# VOLTAGE_PEAK_V2.net
KiCad netlist of a schematic drawn in Altium Designer
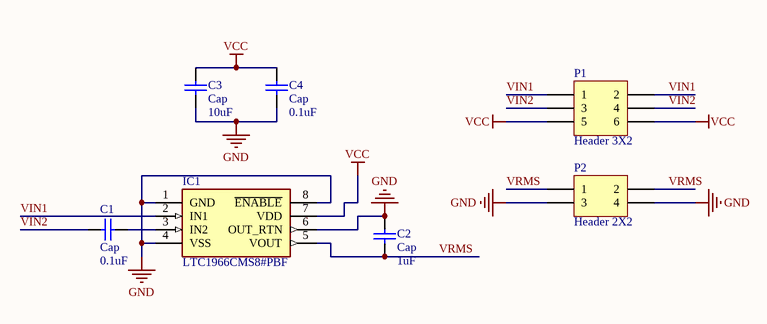
[diagram p0: VOLTAGE_PEAK_V2.SchDoc]

(export (version "E")
  (design (tool "Eeschema 10.0.6"))
  (components
    (comp (ref "C1")
      (value "Cap")
      (footprint "1608[0603]")
      (description "Capacitor")
      (fields (field (name "ALTIUM_VALUE") "0.1uF") (field (name "PUBLISHER") "Altium Limited"))
      (libsource (lib "Miscellaneous Devices") (part "Cap"))
    )
    (comp (ref "C2")
      (value "Cap")
      (footprint "1608[0603]")
      (description "Capacitor")
      (fields (field (name "ALTIUM_VALUE") "1uF") (field (name "PUBLISHER") "Altium Limited"))
      (libsource (lib "Miscellaneous Devices") (part "Cap"))
    )
    (comp (ref "C3")
      (value "Cap")
      (footprint "1608[0603]")
      (description "Capacitor")
      (fields (field (name "ALTIUM_VALUE") "10uF") (field (name "PUBLISHER") "Altium Limited"))
      (libsource (lib "Miscellaneous Devices") (part "Cap"))
    )
    (comp (ref "C4")
      (value "Cap")
      (footprint "1608[0603]")
      (description "Capacitor")
      (fields (field (name "ALTIUM_VALUE") "0.1uF") (field (name "PUBLISHER") "Altium Limited"))
      (libsource (lib "Miscellaneous Devices") (part "Cap"))
    )
    (comp (ref "IC1")
      (value "LTC1966CMS8#PBF")
      (footprint "SamacSys:SOP65P490X110-8N")
      (description "Integrated Circuit")
      (fields (field (name "RS PART NUMBER") "7619266P"))
      (libsource (lib "*") (part "LTC1966CMS8#PBF"))
    )
    (comp (ref "P1")
      (value "Header 3X2")
      (footprint "HDR2X3")
      (description "Header, 3-Pin, Dual row")
      (fields (field (name "PUBLISHER") "Altium Limited"))
      (libsource (lib "Miscellaneous Connectors") (part "Header 3X2"))
    )
    (comp (ref "P2")
      (value "Header 2X2")
      (footprint "HDR2X2")
      (description "Header, 2-Pin, Dual row")
      (fields (field (name "PUBLISHER") "Altium Limited"))
      (libsource (lib "Miscellaneous Connectors") (part "Header 2X2"))
    )
  )
  (nets
    (net (code "1") (name "/VIN1") (class "Default")
      (node (ref "IC1") (pin "2") (pinfunction "IN1_2") (pintype "input"))
      (node (ref "P1") (pin "1") (pinfunction "1_1") (pintype "passive"))
      (node (ref "P1") (pin "2") (pinfunction "2_2") (pintype "passive"))
    )
    (net (code "2") (name "/VIN2") (class "Default")
      (node (ref "C1") (pin "1") (pinfunction "1_1") (pintype "passive"))
      (node (ref "P1") (pin "3") (pinfunction "3_3") (pintype "passive"))
      (node (ref "P1") (pin "4") (pinfunction "4_4") (pintype "passive"))
    )
    (net (code "3") (name "/VRMS") (class "Default")
      (node (ref "C2") (pin "1") (pinfunction "1_1") (pintype "passive"))
      (node (ref "IC1") (pin "5") (pinfunction "VOUT_5") (pintype "output"))
      (node (ref "P2") (pin "1") (pinfunction "1_1") (pintype "passive"))
      (node (ref "P2") (pin "2") (pinfunction "2_2") (pintype "passive"))
    )
    (net (code "4") (name "GND") (class "Default")
      (node (ref "C2") (pin "2") (pinfunction "2_2") (pintype "passive"))
      (node (ref "C3") (pin "1") (pinfunction "1_1") (pintype "passive"))
      (node (ref "C4") (pin "1") (pinfunction "1_1") (pintype "passive"))
      (node (ref "IC1") (pin "1") (pinfunction "GND_1") (pintype "power_in"))
      (node (ref "IC1") (pin "4") (pinfunction "VSS_4") (pintype "power_in"))
      (node (ref "IC1") (pin "6") (pinfunction "OUT_RTN_6") (pintype "output"))
      (node (ref "IC1") (pin "8") (pinfunction "~{ENABLE}_8") (pintype "passive"))
      (node (ref "P2") (pin "3") (pinfunction "3_3") (pintype "passive"))
      (node (ref "P2") (pin "4") (pinfunction "4_4") (pintype "passive"))
    )
    (net (code "5") (name "Net-(IC1-IN2)") (class "Default")
      (node (ref "C1") (pin "2") (pinfunction "2_2") (pintype "passive"))
      (node (ref "IC1") (pin "3") (pinfunction "IN2_3") (pintype "input"))
    )
    (net (code "6") (name "VCC") (class "Default")
      (node (ref "C3") (pin "2") (pinfunction "2_2") (pintype "passive"))
      (node (ref "C4") (pin "2") (pinfunction "2_2") (pintype "passive"))
      (node (ref "IC1") (pin "7") (pinfunction "VDD_7") (pintype "power_in"))
      (node (ref "P1") (pin "5") (pinfunction "5_5") (pintype "passive"))
      (node (ref "P1") (pin "6") (pinfunction "6_6") (pintype "passive"))
    )
  )
)
